# 13_16.net
KiCad netlist of a schematic drawn in Altium Designer
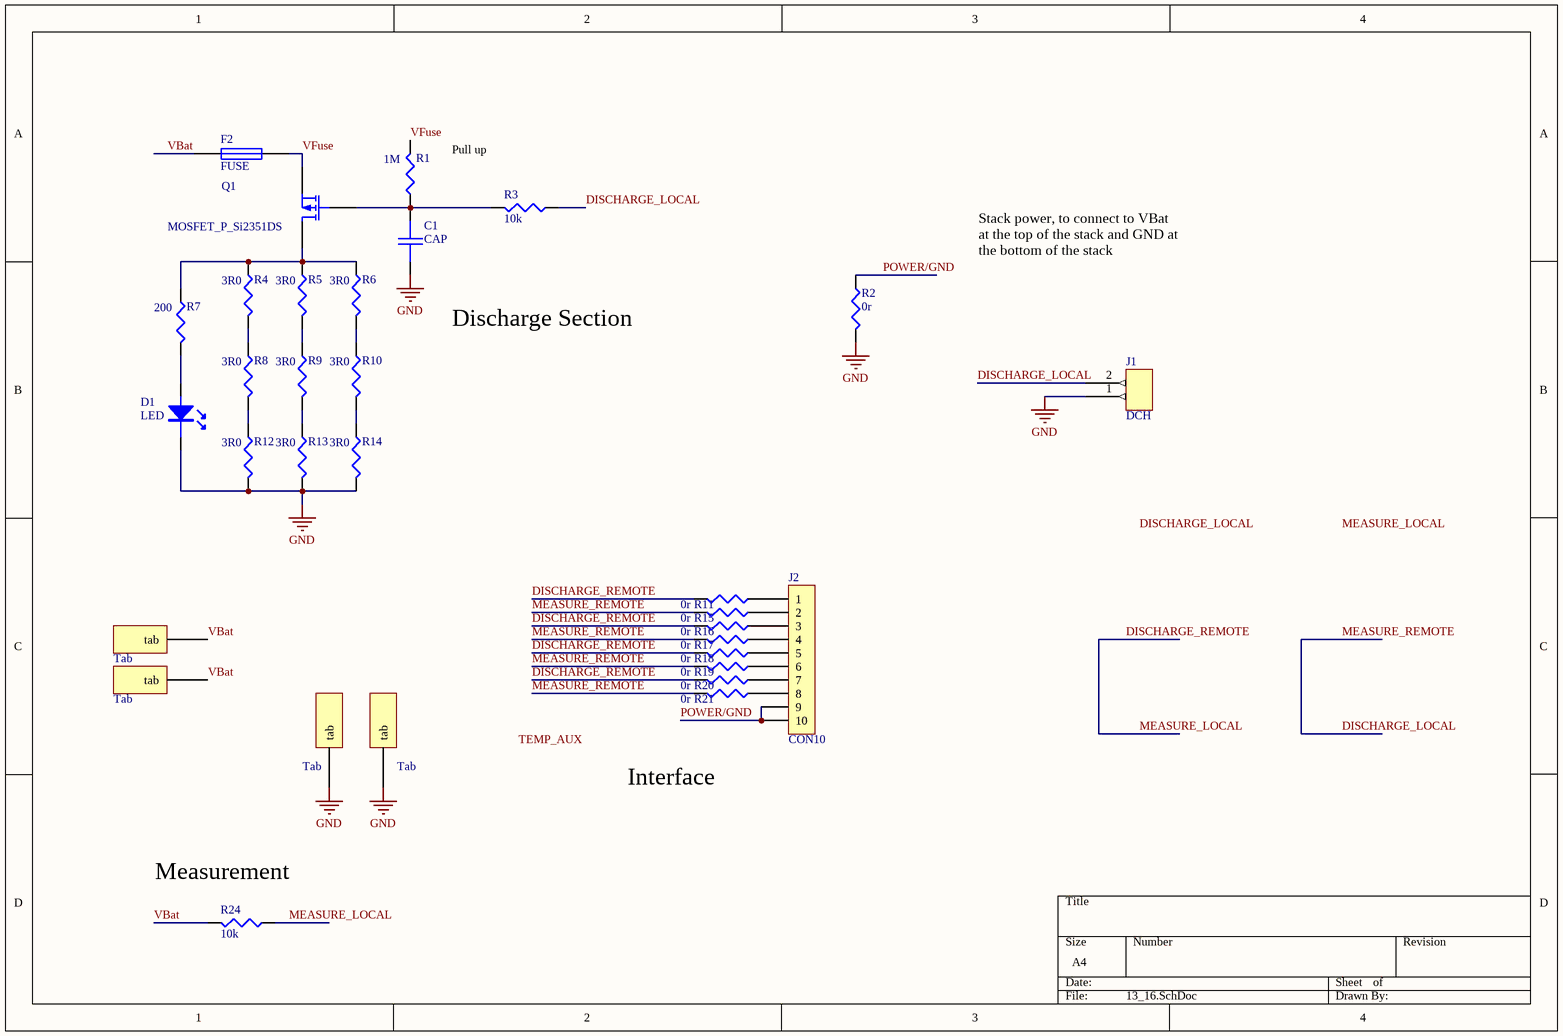
[diagram p0: 13_16.SchDoc]

(export (version "E")
  (design (tool "Eeschema 10.0.6"))
  (components
    (comp (ref "C1")
      (value "CAP")
      (footprint "0603")
      (description "Capacitor")
      (libsource (lib "RCLDQ") (part "CAP"))
    )
    (comp (ref "D1") (value "LED") (footprint "0805LED") (libsource (lib "RCLDQ") (part "LED")))
    (comp (ref "F2")
      (value "FUSE")
      (footprint "LITTELFUSE-154")
      (description "Fuse")
      (libsource (lib "Miscellaneous") (part "FUSE"))
    )
    (comp (ref "J1") (value "DCH") (footprint "IDC2") (libsource (lib "Connectors") (part "CON2")))
    (comp (ref "J2")
      (value "CON10")
      (footprint "IDC10")
      (description "10 pin, right angle, ribbon con with claws")
      (libsource (lib "Connectors") (part "CON10"))
    )
    (comp (ref "J4") (value "Tab") (footprint "tab_connect") (libsource (lib "BMS") (part "tab_connection")))
    (comp (ref "J5") (value "Tab") (footprint "tab_connect") (libsource (lib "BMS") (part "tab_connection")))
    (comp (ref "J6") (value "Tab") (footprint "tab_connect") (libsource (lib "") (part "tab_connection_1")))
    (comp (ref "J7") (value "Tab") (footprint "tab_connect") (libsource (lib "") (part "tab_connection_1")))
    (comp (ref "Q1")
      (value "MOSFET_P_Si2351DS")
      (footprint "SOT23-3")
      (description "Si2351DS P-Channel MOSFET")
      (fields (field (name "PUBLISHER") "Altium Limited"))
      (libsource (lib "RCLDQ") (part "MOSFET_P_Si2351DS"))
    )
    (comp (ref "R1")
      (value "~")
      (footprint "0603")
      (description "Resistor")
      (fields (field (name "RESISTANCE") "1M"))
      (libsource (lib "RCLDQ") (part "RES1"))
    )
    (comp (ref "R2")
      (value "~")
      (footprint "1206")
      (description "Resistor")
      (fields (field (name "RESISTANCE") "0r"))
      (libsource (lib "RCLDQ") (part "RES1"))
    )
    (comp (ref "R3")
      (value "~")
      (footprint "0603")
      (description "Resistor")
      (fields (field (name "RESISTANCE") "10k"))
      (libsource (lib "RCLDQ") (part "RES1"))
    )
    (comp (ref "R4")
      (value "3R0")
      (footprint "2512")
      (description "Resistor")
      (libsource (lib "RCLDQ") (part "RES1"))
    )
    (comp (ref "R5")
      (value "3R0")
      (footprint "2512")
      (description "Resistor")
      (libsource (lib "RCLDQ") (part "RES1"))
    )
    (comp (ref "R6")
      (value "3R0")
      (footprint "2512")
      (description "Resistor")
      (libsource (lib "RCLDQ") (part "RES1"))
    )
    (comp (ref "R7")
      (value "200")
      (footprint "0603")
      (description "Resistor")
      (libsource (lib "RCLDQ") (part "RES1"))
    )
    (comp (ref "R8")
      (value "3R0")
      (footprint "2512")
      (description "Resistor")
      (libsource (lib "RCLDQ") (part "RES1"))
    )
    (comp (ref "R9")
      (value "3R0")
      (footprint "2512")
      (description "Resistor")
      (libsource (lib "RCLDQ") (part "RES1"))
    )
    (comp (ref "R10")
      (value "3R0")
      (footprint "2512")
      (description "Resistor")
      (libsource (lib "RCLDQ") (part "RES1"))
    )
    (comp (ref "R11")
      (value "~")
      (footprint "0603")
      (description "Resistor")
      (fields (field (name "RESISTANCE") "0r"))
      (libsource (lib "RCLDQ") (part "RES1"))
    )
    (comp (ref "R12")
      (value "3R0")
      (footprint "2512")
      (description "Resistor")
      (libsource (lib "RCLDQ") (part "RES1"))
    )
    (comp (ref "R13")
      (value "3R0")
      (footprint "2512")
      (description "Resistor")
      (libsource (lib "RCLDQ") (part "RES1"))
    )
    (comp (ref "R14")
      (value "3R0")
      (footprint "2512")
      (description "Resistor")
      (libsource (lib "RCLDQ") (part "RES1"))
    )
    (comp (ref "R15")
      (value "~")
      (footprint "0603")
      (description "Resistor")
      (fields (field (name "RESISTANCE") "0r"))
      (libsource (lib "RCLDQ") (part "RES1"))
    )
    (comp (ref "R16")
      (value "~")
      (footprint "0603")
      (description "Resistor")
      (fields (field (name "RESISTANCE") "0r"))
      (libsource (lib "RCLDQ") (part "RES1"))
    )
    (comp (ref "R17")
      (value "~")
      (footprint "0603")
      (description "Resistor")
      (fields (field (name "RESISTANCE") "0r"))
      (libsource (lib "RCLDQ") (part "RES1"))
    )
    (comp (ref "R18")
      (value "~")
      (footprint "0603")
      (description "Resistor")
      (fields (field (name "RESISTANCE") "0r"))
      (libsource (lib "RCLDQ") (part "RES1"))
    )
    (comp (ref "R19")
      (value "~")
      (footprint "0603")
      (description "Resistor")
      (fields (field (name "RESISTANCE") "0r"))
      (libsource (lib "RCLDQ") (part "RES1"))
    )
    (comp (ref "R20")
      (value "~")
      (footprint "0603")
      (description "Resistor")
      (fields (field (name "RESISTANCE") "0r"))
      (libsource (lib "RCLDQ") (part "RES1"))
    )
    (comp (ref "R21")
      (value "~")
      (footprint "0603")
      (description "Resistor")
      (fields (field (name "RESISTANCE") "0r"))
      (libsource (lib "RCLDQ") (part "RES1"))
    )
    (comp (ref "R24")
      (value "~")
      (footprint "0603")
      (description "Resistor")
      (fields (field (name "RESISTANCE") "10k"))
      (libsource (lib "RCLDQ") (part "RES1"))
    )
  )
  (nets
    (net (code "1") (name "/DISCHARGE_LOCAL") (class "Default")
      (node (ref "J1") (pin "2") (pinfunction "2_2") (pintype "output"))
      (node (ref "R15") (pin "2") (pinfunction "2_2") (pintype "passive"))
      (node (ref "R17") (pin "2") (pinfunction "2_2") (pintype "passive"))
      (node (ref "R19") (pin "2") (pinfunction "2_2") (pintype "passive"))
      (node (ref "R21") (pin "2") (pinfunction "2_2") (pintype "passive"))
      (node (ref "R3") (pin "1") (pinfunction "1_1") (pintype "passive"))
    )
    (net (code "2") (name "/DISCHARGE_REMOTE") (class "Default")
      (node (ref "R11") (pin "2") (pinfunction "2_2") (pintype "passive"))
      (node (ref "R16") (pin "2") (pinfunction "2_2") (pintype "passive"))
      (node (ref "R18") (pin "2") (pinfunction "2_2") (pintype "passive"))
      (node (ref "R20") (pin "2") (pinfunction "2_2") (pintype "passive"))
      (node (ref "R24") (pin "1") (pinfunction "1_1") (pintype "passive"))
    )
    (net (code "3") (name "/POWER{slash}GND") (class "Default")
      (node (ref "J2") (pin "10") (pinfunction "10_10") (pintype "passive"))
      (node (ref "J2") (pin "9") (pinfunction "9_9") (pintype "passive"))
      (node (ref "R2") (pin "1") (pinfunction "1_1") (pintype "passive"))
    )
    (net (code "5") (name "/VBat") (class "Default")
      (node (ref "F2") (pin "1") (pinfunction "1_1") (pintype "passive"))
      (node (ref "J4") (pin "0") (pinfunction "tab_0") (pintype "passive"))
      (node (ref "J5") (pin "0") (pinfunction "tab_0") (pintype "passive"))
      (node (ref "R24") (pin "2") (pinfunction "2_2") (pintype "passive"))
    )
    (net (code "6") (name "/VFuse") (class "Default")
      (node (ref "F2") (pin "2") (pinfunction "2_2") (pintype "passive"))
      (node (ref "Q1") (pin "2") (pinfunction "S_2") (pintype "passive"))
      (node (ref "R1") (pin "2") (pinfunction "2_2") (pintype "passive"))
    )
    (net (code "7") (name "GND") (class "Default")
      (node (ref "C1") (pin "2") (pinfunction "2_2") (pintype "passive"))
      (node (ref "D1") (pin "K") (pinfunction "K_K") (pintype "passive"))
      (node (ref "J1") (pin "1") (pinfunction "1_1") (pintype "output"))
      (node (ref "J6") (pin "0") (pinfunction "tab_0") (pintype "passive"))
      (node (ref "J7") (pin "0") (pinfunction "tab_0") (pintype "passive"))
      (node (ref "R12") (pin "2") (pinfunction "2_2") (pintype "passive"))
      (node (ref "R13") (pin "2") (pinfunction "2_2") (pintype "passive"))
      (node (ref "R14") (pin "2") (pinfunction "2_2") (pintype "passive"))
      (node (ref "R2") (pin "2") (pinfunction "2_2") (pintype "passive"))
    )
    (net (code "8") (name "Net-(D1-PadA)") (class "Default")
      (node (ref "D1") (pin "A") (pinfunction "A_A") (pintype "passive"))
      (node (ref "R7") (pin "2") (pinfunction "2_2") (pintype "passive"))
    )
    (net (code "9") (name "Net-(J2-Pad1)") (class "Default")
      (node (ref "J2") (pin "1") (pinfunction "1_1") (pintype "passive"))
      (node (ref "R11") (pin "1") (pinfunction "1_1") (pintype "passive"))
    )
    (net (code "10") (name "Net-(J2-Pad2)") (class "Default")
      (node (ref "J2") (pin "2") (pinfunction "2_2") (pintype "passive"))
      (node (ref "R15") (pin "1") (pinfunction "1_1") (pintype "passive"))
    )
    (net (code "11") (name "Net-(J2-Pad3)") (class "Default")
      (node (ref "J2") (pin "3") (pinfunction "3_3") (pintype "passive"))
      (node (ref "R16") (pin "1") (pinfunction "1_1") (pintype "passive"))
    )
    (net (code "12") (name "Net-(J2-Pad4)") (class "Default")
      (node (ref "J2") (pin "4") (pinfunction "4_4") (pintype "passive"))
      (node (ref "R17") (pin "1") (pinfunction "1_1") (pintype "passive"))
    )
    (net (code "13") (name "Net-(J2-Pad5)") (class "Default")
      (node (ref "J2") (pin "5") (pinfunction "5_5") (pintype "passive"))
      (node (ref "R18") (pin "1") (pinfunction "1_1") (pintype "passive"))
    )
    (net (code "14") (name "Net-(J2-Pad6)") (class "Default")
      (node (ref "J2") (pin "6") (pinfunction "6_6") (pintype "passive"))
      (node (ref "R19") (pin "1") (pinfunction "1_1") (pintype "passive"))
    )
    (net (code "15") (name "Net-(J2-Pad7)") (class "Default")
      (node (ref "J2") (pin "7") (pinfunction "7_7") (pintype "passive"))
      (node (ref "R20") (pin "1") (pinfunction "1_1") (pintype "passive"))
    )
    (net (code "16") (name "Net-(J2-Pad8)") (class "Default")
      (node (ref "J2") (pin "8") (pinfunction "8_8") (pintype "passive"))
      (node (ref "R21") (pin "1") (pinfunction "1_1") (pintype "passive"))
    )
    (net (code "17") (name "Net-(Q1-D)") (class "Default")
      (node (ref "Q1") (pin "3") (pinfunction "D_3") (pintype "passive"))
      (node (ref "R4") (pin "1") (pinfunction "1_1") (pintype "passive"))
      (node (ref "R5") (pin "1") (pinfunction "1_1") (pintype "passive"))
      (node (ref "R6") (pin "1") (pinfunction "1_1") (pintype "passive"))
      (node (ref "R7") (pin "1") (pinfunction "1_1") (pintype "passive"))
    )
    (net (code "18") (name "Net-(Q1-G)") (class "Default")
      (node (ref "C1") (pin "1") (pinfunction "1_1") (pintype "passive"))
      (node (ref "Q1") (pin "1") (pinfunction "G_1") (pintype "passive"))
      (node (ref "R1") (pin "1") (pinfunction "1_1") (pintype "passive"))
      (node (ref "R3") (pin "2") (pinfunction "2_2") (pintype "passive"))
    )
    (net (code "19") (name "Net-(R4-Pad2)") (class "Default")
      (node (ref "R4") (pin "2") (pinfunction "2_2") (pintype "passive"))
      (node (ref "R8") (pin "1") (pinfunction "1_1") (pintype "passive"))
    )
    (net (code "20") (name "Net-(R5-Pad2)") (class "Default")
      (node (ref "R5") (pin "2") (pinfunction "2_2") (pintype "passive"))
      (node (ref "R9") (pin "1") (pinfunction "1_1") (pintype "passive"))
    )
    (net (code "21") (name "Net-(R10-Pad1)") (class "Default")
      (node (ref "R10") (pin "1") (pinfunction "1_1") (pintype "passive"))
      (node (ref "R6") (pin "2") (pinfunction "2_2") (pintype "passive"))
    )
    (net (code "22") (name "Net-(R10-Pad2)") (class "Default")
      (node (ref "R10") (pin "2") (pinfunction "2_2") (pintype "passive"))
      (node (ref "R14") (pin "1") (pinfunction "1_1") (pintype "passive"))
    )
    (net (code "23") (name "Net-(R12-Pad1)") (class "Default")
      (node (ref "R12") (pin "1") (pinfunction "1_1") (pintype "passive"))
      (node (ref "R8") (pin "2") (pinfunction "2_2") (pintype "passive"))
    )
    (net (code "24") (name "Net-(R13-Pad1)") (class "Default")
      (node (ref "R13") (pin "1") (pinfunction "1_1") (pintype "passive"))
      (node (ref "R9") (pin "2") (pinfunction "2_2") (pintype "passive"))
    )
  )
)
